# Lights_Board.net
KiCad netlist of a schematic drawn in Altium Designer
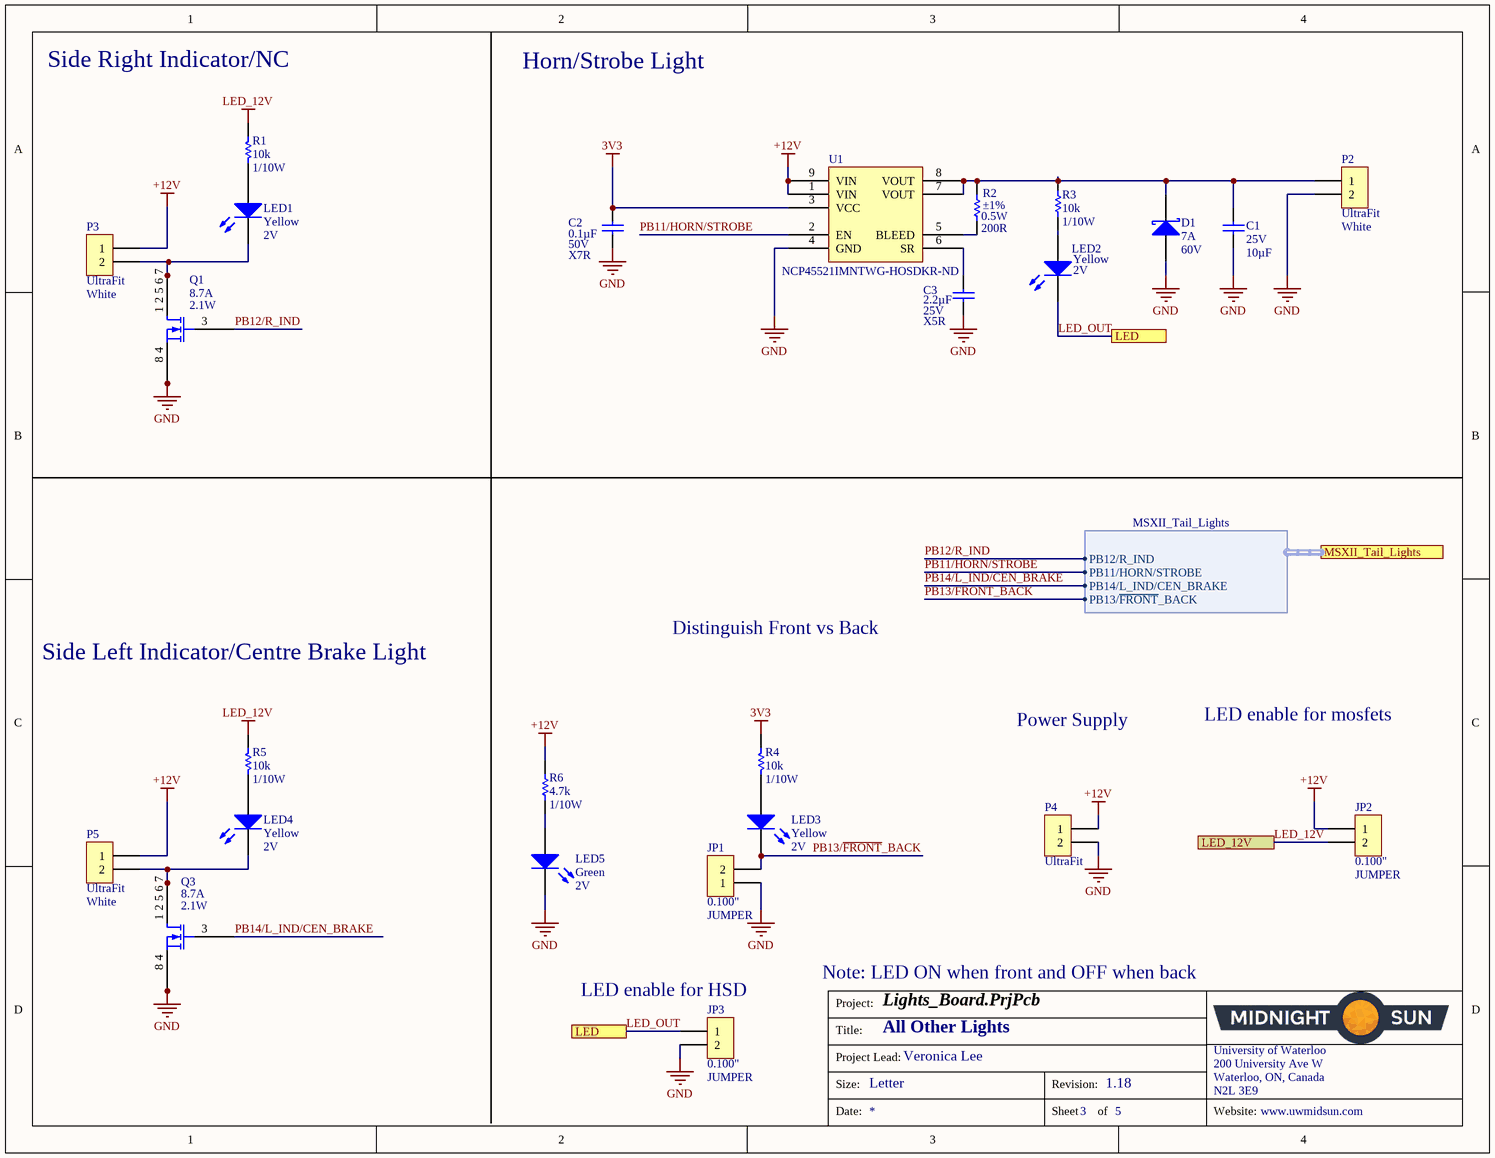
[diagram p0: Lights_Board.SchDoc]

(export (version "E")
  (design (tool "Eeschema 10.0.6"))
  (components
    (comp (ref "C1")
      (value "CAP CER 10uF 25V 10% X5R 0805")
      (footprint "CAP, 0805")
      (description "10µF ±10% 25V Ceramic Capacitor X5R 0805 (2012 Metric)")
      (fields
        (field (name "MANUFACTURER") "Murata Electronics North America")
        (field (name "MANUFACTURER PART NUMBER") "GRM21BR61E106KA73L")
        (field (name "VOLTAGE - RATED") "25V")
        (field (name "CAPACITANCE") "10µF")
      )
      (libsource (lib "Schematic Diagrams") (part "CAP CER 10uF 25V 10% X5R 0805"))
    )
    (comp (ref "C2")
      (value "CAP CER 0.1UF 50V 10% X7R 0603")
      (footprint "CAP, 0603")
      (description "0.10µF ±10% 50V Ceramic Capacitor X7R 0603 (1608 Metric)")
      (fields
        (field (name "TOLERANCE") "±10%")
        (field (name "CAPACITANCE") "0.1µF")
        (field (name "VOLTAGE") "50V")
        (field (name "TEMPERATURE COEFFICIENT") "X7R")
      )
      (libsource (lib "Schematic Diagrams") (part "CAP CER 0.1UF 50V 10% X7R 0603"))
    )
    (comp (ref "C3")
      (value "CAP CER 2.2UF 25V 10% X5R 0603")
      (footprint "CAP, 0603")
      (description "2.2µF ±10% 25V Ceramic Capacitor X5R 0603 (1608 Metric)")
      (fields
        (field (name "TOLERANCE") "±10%")
        (field (name "CAPACITANCE") "2.2µF")
        (field (name "VOLTAGE") "25V")
        (field (name "TEMPERATURE COEFFICIENT") "X5R")
      )
      (libsource (lib "Schematic Diagrams") (part "CAP CER 2.2UF 25V 10% X5R 0603"))
    )
    (comp (ref "D1")
      (value "DIODE SCHOTTKY 60V 7A POWERDI5")
      (footprint "DIODE SCHOTTKY 60V 7A POWERDI5")
      (description "Diode Schottky 60V 7A Surface Mount PowerDI™ 5")
      (fields
        (field (name "MANUFACTURER") "Diodes Incorporated")
        (field (name "MANUFACTURER PART NUMBER") "PDS760Q-13")
        (field (name "CURRENT - AVERAGE RECTIFIED (IO)") "7A")
        (field (name "VOLTAGE") "60V")
      )
      (libsource (lib "Schematic Diagrams") (part "DIODE SCHOTTKY 60V 7A POWERDI5"))
    )
    (comp (ref "JP1")
      (value "JUMPER")
      (footprint "CONN 2POS JUMPER 0.1\"")
      (description "2 Positions Header Connector Through Hole Gold")
      (fields
        (field (name "MANUFACTURER") "Omron Electronics Inc-EMC Div")
        (field (name "MANUFACTURER PART NUMBER") "XG8T-0231")
        (field (name "ROW SPACING - MATING") "0.100\"")
        (field (name "TYPE") "JUMPER")
      )
      (libsource (lib "") (part "CONN 2POS JUMPER 0.1{dblquote}_1"))
    )
    (comp (ref "JP2")
      (value "JUMPER")
      (footprint "CONN 2POS JUMPER 0.1\"")
      (description "2 Positions Header Connector Through Hole Gold")
      (fields
        (field (name "MANUFACTURER") "Omron Electronics Inc-EMC Div")
        (field (name "MANUFACTURER PART NUMBER") "XG8T-0231")
        (field (name "ROW SPACING - MATING") "0.100\"")
        (field (name "TYPE") "JUMPER")
      )
      (libsource (lib "Schematic Diagrams") (part "CONN 2POS JUMPER 0.1{dblquote}"))
    )
    (comp (ref "JP3")
      (value "JUMPER")
      (footprint "CONN 2POS JUMPER 0.1\"")
      (description "2 Positions Header Connector Through Hole Gold")
      (fields
        (field (name "MANUFACTURER") "Omron Electronics Inc-EMC Div")
        (field (name "MANUFACTURER PART NUMBER") "XG8T-0231")
        (field (name "ROW SPACING - MATING") "0.100\"")
        (field (name "TYPE") "JUMPER")
      )
      (libsource (lib "Schematic Diagrams") (part "CONN 2POS JUMPER 0.1{dblquote}"))
    )
    (comp (ref "LED1")
      (value "LED YELLOW CLEAR 2.1V 0603")
      (footprint "LED_0603")
      (description "Yellow 590nm LED Indication - Discrete 2V 0603 (1608 Metric)")
      (fields
        (field (name "MANUFACTURER") "Wurth Electronics Inc.")
        (field (name "MANUFACTURER PART NUMBER") "150060YS75000")
        (field (name "COLOR") "Yellow")
        (field (name "VOLTAGE - FORWARD (VF) (TYP)") "2V")
      )
      (libsource (lib "Schematic Diagrams") (part "LED YELLOW CLEAR 2.1V 0603"))
    )
    (comp (ref "LED2")
      (value "LED YELLOW CLEAR 2.1V 0603")
      (footprint "LED_0603")
      (description "Yellow 590nm LED Indication - Discrete 2V 0603 (1608 Metric)")
      (fields
        (field (name "MANUFACTURER") "Wurth Electronics Inc.")
        (field (name "MANUFACTURER PART NUMBER") "150060YS75000")
        (field (name "COLOR") "Yellow")
        (field (name "VOLTAGE - FORWARD (VF) (TYP)") "2V")
      )
      (libsource (lib "Schematic Diagrams") (part "LED YELLOW CLEAR 2.1V 0603"))
    )
    (comp (ref "LED3")
      (value "LED YELLOW CLEAR 2.1V 0603")
      (footprint "LED_0603")
      (description "Yellow 590nm LED Indication - Discrete 2V 0603 (1608 Metric)")
      (fields
        (field (name "MANUFACTURER") "Wurth Electronics Inc.")
        (field (name "MANUFACTURER PART NUMBER") "150060YS75000")
        (field (name "COLOR") "Yellow")
        (field (name "VOLTAGE - FORWARD (VF) (TYP)") "2V")
      )
      (libsource (lib "Schematic Diagrams") (part "LED YELLOW CLEAR 2.1V 0603"))
    )
    (comp (ref "LED4")
      (value "LED YELLOW CLEAR 2.1V 0603")
      (footprint "LED_0603")
      (description "Yellow 590nm LED Indication - Discrete 2V 0603 (1608 Metric)")
      (fields
        (field (name "MANUFACTURER") "Wurth Electronics Inc.")
        (field (name "MANUFACTURER PART NUMBER") "150060YS75000")
        (field (name "COLOR") "Yellow")
        (field (name "VOLTAGE - FORWARD (VF) (TYP)") "2V")
      )
      (libsource (lib "Schematic Diagrams") (part "LED YELLOW CLEAR 2.1V 0603"))
    )
    (comp (ref "LED5")
      (value "LED GREEN CLEAR 2V 0603")
      (footprint "LED_0603")
      (description "Green 572nm LED Indication - Discrete 2V 0603 (1608 Metric)")
      (fields
        (field (name "MANUFACTURER") "Wurth Electronics Inc.")
        (field (name "MANUFACTURER PART NUMBER") "150060VS75000")
        (field (name "COLOR") "Green")
        (field (name "VOLTAGE - FORWARD (VF) (TYP)") "2V")
      )
      (libsource (lib "Schematic Diagrams") (part "LED GREEN CLEAR 2V 0603"))
    )
    (comp (ref "P2")
      (value "CONN 2POS ULTRA-FIT NATURAL COLOR 0.138\"")
      (footprint "CONN, 2POS ULTRA-FIT - NATURAL COLOR")
      (description "2 Positions Header, Shrouded Connector 0.138\" (3.50mm) Through Hole")
      (fields
        (field (name "VOLTAGE") "400V")
        (field (name "SERIES") "UltraFit")
        (field (name "COLOR") "White")
      )
      (libsource (lib "") (part "CONN 2POS ULTRA-FIT NATURAL COLOR 0.138{dblquote}_1"))
    )
    (comp (ref "P3")
      (value "CONN 2POS ULTRA-FIT NATURAL COLOR 0.138\"")
      (footprint "CONN, 2POS ULTRA-FIT - NATURAL COLOR")
      (description "2 Positions Header, Shrouded Connector 0.138\" (3.50mm) Through Hole")
      (fields
        (field (name "VOLTAGE") "400V")
        (field (name "SERIES") "UltraFit")
        (field (name "COLOR") "White")
      )
      (libsource (lib "Schematic Diagrams") (part "CONN 2POS ULTRA-FIT NATURAL COLOR 0.138{dblquote}"))
    )
    (comp (ref "P4")
      (value "CONN 2POS ULTRA-FIT 0.138\"")
      (footprint "CONN, 2POS ULTRA-FIT")
      (description "2 Positions Header, Shrouded Connector 0.138\" (3.50mm) Through Hole Gold")
      (fields (field (name "VOLTAGE") "400V") (field (name "SERIES") "UltraFit"))
      (libsource (lib "Schematic Diagrams") (part "CONN 2POS ULTRA-FIT 0.138{dblquote}"))
    )
    (comp (ref "P5")
      (value "CONN 2POS ULTRA-FIT NATURAL COLOR 0.138\"")
      (footprint "CONN, 2POS ULTRA-FIT - NATURAL COLOR")
      (description "2 Positions Header, Shrouded Connector 0.138\" (3.50mm) Through Hole")
      (fields
        (field (name "VOLTAGE") "400V")
        (field (name "SERIES") "UltraFit")
        (field (name "COLOR") "White")
      )
      (libsource (lib "Schematic Diagrams") (part "CONN 2POS ULTRA-FIT NATURAL COLOR 0.138{dblquote}"))
    )
    (comp (ref "Q1")
      (value "MOSFET N-CH 30V 8.7A 2.1W 6-PQFN (2x2)")
      (footprint "MOSFET N-CH 30V 12A 2mmx2mm PQFN")
      (description "N-Channel 30V 8.7A (Ta), 19A (Tc) 2.1W (Ta) Surface Mount 6-PQFN (2x2)")
      (fields
        (field (name "CURRENT - CONTINUOUS DRAIN (ID) @ 25°C") "8.7A")
        (field (name "POWER DISSIPATION (MAX)") "2.1W")
      )
      (libsource (lib "Schematic Diagrams") (part "MOSFET N-CH 30V 8.7A 2.1W 6-PQFN (2x2)"))
    )
    (comp (ref "Q3")
      (value "MOSFET N-CH 30V 8.7A 2.1W 6-PQFN (2x2)")
      (footprint "MOSFET N-CH 30V 12A 2mmx2mm PQFN")
      (description "N-Channel 30V 8.7A (Ta), 19A (Tc) 2.1W (Ta) Surface Mount 6-PQFN (2x2)")
      (fields
        (field (name "CURRENT - CONTINUOUS DRAIN (ID) @ 25°C") "8.7A")
        (field (name "POWER DISSIPATION (MAX)") "2.1W")
      )
      (libsource (lib "Schematic Diagrams") (part "MOSFET N-CH 30V 8.7A 2.1W 6-PQFN (2x2)"))
    )
    (comp (ref "R1")
      (value "RES 10K OHM 1% 1/10W 0603")
      (footprint "RES, 0603")
      (description "RES SMD 10K OHM 1% 1/10W 0603")
      (fields
        (field (name "TOLERANCE") "±1%")
        (field (name "RESISTANCE") "10k")
        (field (name "POWER") "1/10W")
      )
      (libsource (lib "Schematic Diagrams") (part "RES 10K OHM 1% 1/10W 0603"))
    )
    (comp (ref "R2")
      (value "RES 200 OHM 5% 1/2W 0805")
      (footprint "RES 0805")
      (fields
        (field (name "MANUFACTURER") "Panasonic Electronic Components")
        (field (name "MANUFACTURER PART NUMBER") "ERJ-P06F2000V")
        (field (name "RESISTANCE") "200R")
        (field (name "TOLERANCE") "±1%")
        (field (name "POWER (WATTS)") "0.5W")
      )
      (libsource (lib "Schematic Diagrams") (part "RES 200 OHM 5% 1/2W 0805"))
    )
    (comp (ref "R3")
      (value "RES 10K OHM 1% 1/10W 0603")
      (footprint "RES, 0603")
      (description "RES SMD 10K OHM 1% 1/10W 0603")
      (fields
        (field (name "TOLERANCE") "±1%")
        (field (name "RESISTANCE") "10k")
        (field (name "POWER") "1/10W")
      )
      (libsource (lib "Schematic Diagrams") (part "RES 10K OHM 1% 1/10W 0603"))
    )
    (comp (ref "R4")
      (value "RES 10K OHM 1% 1/10W 0603")
      (footprint "RES, 0603")
      (description "RES SMD 10K OHM 1% 1/10W 0603")
      (fields
        (field (name "TOLERANCE") "±1%")
        (field (name "RESISTANCE") "10k")
        (field (name "POWER") "1/10W")
      )
      (libsource (lib "Schematic Diagrams") (part "RES 10K OHM 1% 1/10W 0603"))
    )
    (comp (ref "R5")
      (value "RES 10K OHM 1% 1/10W 0603")
      (footprint "RES, 0603")
      (description "RES SMD 10K OHM 1% 1/10W 0603")
      (fields
        (field (name "TOLERANCE") "±1%")
        (field (name "RESISTANCE") "10k")
        (field (name "POWER") "1/10W")
      )
      (libsource (lib "Schematic Diagrams") (part "RES 10K OHM 1% 1/10W 0603"))
    )
    (comp (ref "R6")
      (value "RES 4.7K OHM 1% 1/10W 0603")
      (footprint "RES, 0603")
      (description "4.7k Ohm ±1% 0.1W, 1/10W Chip Resistor 0603 (1608 Metric) Moisture Resistant Thick Film")
      (fields
        (field (name "TOLERANCE") "±1%")
        (field (name "RESISTANCE (OHMS)") "4.7k")
        (field (name "POWER (WATTS)") "1/10W")
      )
      (libsource (lib "Schematic Diagrams") (part "RES 4.7K OHM 1% 1/10W 0603"))
    )
    (comp (ref "U1")
      (value "IC LOAD SWITCH ACT-HI 10.5A 8DFN")
      (footprint "IC LOAD SWITCH ACT-HI 10.5A 8DFN")
      (description "NCP45521IMNTWG-H")
      (fields
        (field (name "MANUFACTURER") "ON Semiconductor")
        (field (name "SUPPLIER PART NUMBER 2") "NCP45521IMNTWG-HOSDKR-ND")
      )
      (libsource (lib "Schematic Diagrams") (part "IC LOAD SWITCH ACT-HI 10.5A 8DFN"))
    )
  )
  (nets
    (net (code "2") (name "+12V") (class "Default")
      (node (ref "JP2") (pin "1") (pinfunction "1_1") (pintype "passive"))
      (node (ref "P3") (pin "1") (pinfunction "1_1") (pintype "passive"))
      (node (ref "P4") (pin "1") (pinfunction "1_1") (pintype "passive"))
      (node (ref "P5") (pin "1") (pinfunction "1_1") (pintype "passive"))
      (node (ref "R6") (pin "1") (pinfunction "1_1") (pintype "passive"))
      (node (ref "U1") (pin "1") (pinfunction "VIN_1") (pintype "passive"))
      (node (ref "U1") (pin "9") (pinfunction "VIN_9") (pintype "passive"))
    )
    (net (code "3") (name "/LED_OUT") (class "Default")
      (node (ref "JP3") (pin "1") (pinfunction "1_1") (pintype "passive"))
      (node (ref "LED2") (pin "2") (pinfunction "K_2") (pintype "passive"))
    )
    (net (code "4") (name "/PB11{slash}HORN{slash}STROBE") (class "Default")
      (node (ref "U1") (pin "2") (pinfunction "EN_2") (pintype "passive"))
    )
    (net (code "5") (name "/PB12{slash}R_IND") (class "Default")
      (node (ref "Q1") (pin "3") (pinfunction "G_3") (pintype "passive"))
    )
    (net (code "6") (name "/PB13{slash}~{FRONT}_BACK") (class "Default")
      (node (ref "JP1") (pin "2") (pinfunction "2_2") (pintype "passive"))
      (node (ref "LED3") (pin "2") (pinfunction "K_2") (pintype "passive"))
    )
    (net (code "7") (name "/PB14{slash}L_IND{slash}CEN_BRAKE") (class "Default")
      (node (ref "Q3") (pin "3") (pinfunction "G_3") (pintype "passive"))
    )
    (net (code "9") (name "3V3") (class "Default")
      (node (ref "C2") (pin "1") (pinfunction "1_1") (pintype "passive"))
      (node (ref "R4") (pin "1") (pinfunction "1_1") (pintype "passive"))
      (node (ref "U1") (pin "3") (pinfunction "VCC_3") (pintype "passive"))
    )
    (net (code "10") (name "GND") (class "Default")
      (node (ref "C1") (pin "2") (pinfunction "2_2") (pintype "passive"))
      (node (ref "C2") (pin "2") (pinfunction "2_2") (pintype "passive"))
      (node (ref "C3") (pin "2") (pinfunction "2_2") (pintype "passive"))
      (node (ref "D1") (pin "1") (pinfunction "1_1") (pintype "passive"))
      (node (ref "JP1") (pin "1") (pinfunction "1_1") (pintype "passive"))
      (node (ref "JP3") (pin "2") (pinfunction "2_2") (pintype "passive"))
      (node (ref "LED5") (pin "2") (pinfunction "K_2") (pintype "passive"))
      (node (ref "P2") (pin "2") (pinfunction "2_2") (pintype "passive"))
      (node (ref "P4") (pin "2") (pinfunction "2_2") (pintype "passive"))
      (node (ref "Q1") (pin "4") (pinfunction "S_4") (pintype "passive"))
      (node (ref "Q1") (pin "8") (pinfunction "S_8") (pintype "passive"))
      (node (ref "Q3") (pin "4") (pinfunction "S_4") (pintype "passive"))
      (node (ref "Q3") (pin "8") (pinfunction "S_8") (pintype "passive"))
      (node (ref "U1") (pin "4") (pinfunction "GND_4") (pintype "passive"))
    )
    (net (code "11") (name "LED_12V") (class "Default")
      (node (ref "JP2") (pin "2") (pinfunction "2_2") (pintype "passive"))
      (node (ref "R1") (pin "1") (pinfunction "1_1") (pintype "passive"))
      (node (ref "R5") (pin "1") (pinfunction "1_1") (pintype "passive"))
    )
    (net (code "12") (name "Net-(C1-Pad1)") (class "Default")
      (node (ref "C1") (pin "1") (pinfunction "1_1") (pintype "passive"))
      (node (ref "D1") (pin "2") (pinfunction "2_2") (pintype "passive"))
      (node (ref "P2") (pin "1") (pinfunction "1_1") (pintype "passive"))
      (node (ref "R2") (pin "1") (pinfunction "1_1") (pintype "passive"))
      (node (ref "R3") (pin "1") (pinfunction "1_1") (pintype "passive"))
      (node (ref "U1") (pin "7") (pinfunction "VOUT_7") (pintype "passive"))
      (node (ref "U1") (pin "8") (pinfunction "VOUT_8") (pintype "passive"))
    )
    (net (code "13") (name "Net-(LED1-A)") (class "Default")
      (node (ref "LED1") (pin "1") (pinfunction "A_1") (pintype "passive"))
      (node (ref "R1") (pin "2") (pinfunction "2_2") (pintype "passive"))
    )
    (net (code "14") (name "Net-(LED1-K)") (class "Default")
      (node (ref "LED1") (pin "2") (pinfunction "K_2") (pintype "passive"))
      (node (ref "P3") (pin "2") (pinfunction "2_2") (pintype "passive"))
      (node (ref "Q1") (pin "1") (pinfunction "D_1") (pintype "passive"))
      (node (ref "Q1") (pin "2") (pinfunction "D_2") (pintype "passive"))
      (node (ref "Q1") (pin "5") (pinfunction "D_5") (pintype "passive"))
      (node (ref "Q1") (pin "6") (pinfunction "D_6") (pintype "passive"))
      (node (ref "Q1") (pin "7") (pinfunction "D_7") (pintype "passive"))
    )
    (net (code "15") (name "Net-(LED2-A)") (class "Default")
      (node (ref "LED2") (pin "1") (pinfunction "A_1") (pintype "passive"))
      (node (ref "R3") (pin "2") (pinfunction "2_2") (pintype "passive"))
    )
    (net (code "16") (name "Net-(LED3-A)") (class "Default")
      (node (ref "LED3") (pin "1") (pinfunction "A_1") (pintype "passive"))
      (node (ref "R4") (pin "2") (pinfunction "2_2") (pintype "passive"))
    )
    (net (code "17") (name "Net-(LED4-A)") (class "Default")
      (node (ref "LED4") (pin "1") (pinfunction "A_1") (pintype "passive"))
      (node (ref "R5") (pin "2") (pinfunction "2_2") (pintype "passive"))
    )
    (net (code "18") (name "Net-(LED4-K)") (class "Default")
      (node (ref "LED4") (pin "2") (pinfunction "K_2") (pintype "passive"))
      (node (ref "P5") (pin "2") (pinfunction "2_2") (pintype "passive"))
      (node (ref "Q3") (pin "1") (pinfunction "D_1") (pintype "passive"))
      (node (ref "Q3") (pin "2") (pinfunction "D_2") (pintype "passive"))
      (node (ref "Q3") (pin "5") (pinfunction "D_5") (pintype "passive"))
      (node (ref "Q3") (pin "6") (pinfunction "D_6") (pintype "passive"))
      (node (ref "Q3") (pin "7") (pinfunction "D_7") (pintype "passive"))
    )
    (net (code "19") (name "Net-(LED5-A)") (class "Default")
      (node (ref "LED5") (pin "1") (pinfunction "A_1") (pintype "passive"))
      (node (ref "R6") (pin "2") (pinfunction "2_2") (pintype "passive"))
    )
    (net (code "20") (name "Net-(U1-BLEED)") (class "Default")
      (node (ref "R2") (pin "2") (pinfunction "2_2") (pintype "passive"))
      (node (ref "U1") (pin "5") (pinfunction "BLEED_5") (pintype "passive"))
    )
    (net (code "21") (name "Net-(U1-SR)") (class "Default")
      (node (ref "C3") (pin "1") (pinfunction "1_1") (pintype "passive"))
      (node (ref "U1") (pin "6") (pinfunction "SR_6") (pintype "passive"))
    )
  )
)
